# molly.net
KiCad netlist of a schematic drawn in Altium Designer
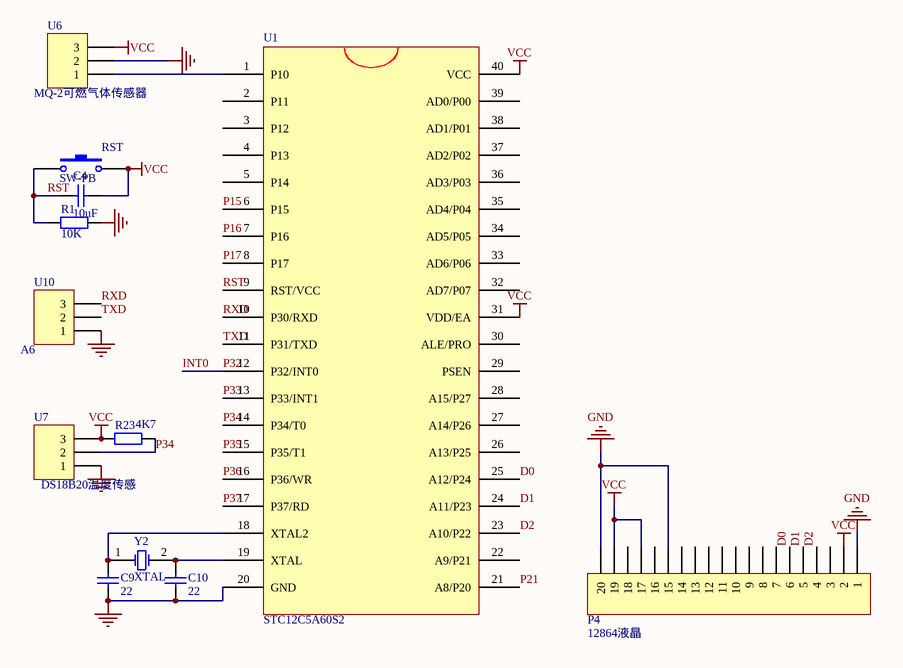
[diagram p0: molly.SchDoc]

(export (version "E")
  (design (tool "Eeschema 10.0.6"))
  (components
    (comp (ref "C4")
      (value "10uF")
      (footprint "CAPR2.54-5.1x3.2")
      (description "Capacitor")
      (fields (field (name "PUBLISHER") "Altium Limited"))
      (libsource (lib "Miscellaneous Devices") (part "cap"))
    )
    (comp (ref "C9")
      (value "22")
      (footprint "2012[0805]")
      (description "Capacitor")
      (fields (field (name "PUBLISHER") "Altium Limited"))
      (libsource (lib "Miscellaneous Devices") (part "Cap"))
    )
    (comp (ref "C10")
      (value "22")
      (footprint "2012[0805]")
      (description "Capacitor")
      (fields (field (name "PUBLISHER") "Altium Limited"))
      (libsource (lib "Miscellaneous Devices") (part "Cap"))
    )
    (comp (ref "P4")
      (value "12864液晶")
      (footprint "HDR1X20")
      (description "Header, 20-Pin")
      (fields (field (name "PUBLISHER") "Altium Limited"))
      (libsource (lib "Miscellaneous Connectors") (part "Header 20"))
    )
    (comp (ref "R1")
      (value "10K")
      (footprint "AXIAL-0.4")
      (description "Resistor")
      (fields (field (name "PUBLISHER") "Altium Limited"))
      (libsource (lib "Miscellaneous Devices") (part "Res2"))
    )
    (comp (ref "R23")
      (value "4K7")
      (footprint "AXIAL-0.4")
      (description "Resistor")
      (fields (field (name "PUBLISHER") "Altium Limited"))
      (libsource (lib "") (part "Res2_1"))
    )
    (comp (ref "RST")
      (value "SW-PB")
      (footprint "KEY_1")
      (description "Switch")
      (fields (field (name "PUBLISHER") "Altium Limited"))
      (libsource (lib "Miscellaneous Devices") (part "SW-PB"))
    )
    (comp (ref "U1")
      (value "STC12C5A60S2")
      (footprint "Dual-In-Line Package:DIP-40")
      (libsource (lib "selfmade") (part "at89s52"))
    )
    (comp (ref "U6")
      (value "MQ-2可燃气体传感器")
      (footprint "HDR1X3")
      (description "Header, 3-Pin")
      (fields (field (name "PUBLISHER") "Altium Limited"))
      (libsource (lib "Miscellaneous Connectors") (part "Header 3"))
    )
    (comp (ref "U7")
      (value "DS18B20温度传感")
      (footprint "HDR1X3")
      (description "Header, 3-Pin")
      (fields (field (name "PUBLISHER") "Altium Limited"))
      (libsource (lib "Miscellaneous Connectors") (part "Header 3"))
    )
    (comp (ref "U10")
      (value "A6")
      (footprint "HDR1X3")
      (description "Header, 3-Pin")
      (fields (field (name "PUBLISHER") "Altium Limited"))
      (libsource (lib "Miscellaneous Connectors") (part "Header 3"))
    )
    (comp (ref "Y2")
      (value "XTAL")
      (footprint "SPST-2")
      (description "Crystal Oscillator")
      (fields (field (name "PUBLISHER") "Altium Limited"))
      (libsource (lib "Miscellaneous Devices") (part "XTAL"))
    )
  )
  (nets
    (net (code "1") (name "/D0") (class "Default")
      (node (ref "P4") (pin "6") (pinfunction "6_6") (pintype "passive"))
      (node (ref "U1") (pin "25") (pinfunction "A12/P24_25") (pintype "passive"))
    )
    (net (code "2") (name "/D1") (class "Default")
      (node (ref "P4") (pin "5") (pinfunction "5_5") (pintype "passive"))
      (node (ref "U1") (pin "24") (pinfunction "A11/P23_24") (pintype "passive"))
    )
    (net (code "3") (name "/D2") (class "Default")
      (node (ref "P4") (pin "4") (pinfunction "4_4") (pintype "passive"))
      (node (ref "U1") (pin "23") (pinfunction "A10/P22_23") (pintype "passive"))
    )
    (net (code "4") (name "/INT0") (class "Default")
      (node (ref "U1") (pin "12") (pinfunction "P32/INT0_12") (pintype "passive"))
    )
    (net (code "5") (name "/P15") (class "Default")
      (node (ref "U1") (pin "6") (pinfunction "P15_6") (pintype "passive"))
    )
    (net (code "6") (name "/P16") (class "Default")
      (node (ref "U1") (pin "7") (pinfunction "P16_7") (pintype "passive"))
    )
    (net (code "7") (name "/P17") (class "Default")
      (node (ref "U1") (pin "8") (pinfunction "P17_8") (pintype "passive"))
    )
    (net (code "8") (name "/P21") (class "Default")
      (node (ref "U1") (pin "21") (pinfunction "A8/P20_21") (pintype "passive"))
    )
    (net (code "9") (name "/P33") (class "Default")
      (node (ref "U1") (pin "13") (pinfunction "P33/INT1_13") (pintype "passive"))
    )
    (net (code "10") (name "/P34") (class "Default")
      (node (ref "R23") (pin "1") (pinfunction "1_1") (pintype "passive"))
      (node (ref "U1") (pin "14") (pinfunction "P34/T0_14") (pintype "passive"))
      (node (ref "U7") (pin "2") (pinfunction "2_2") (pintype "passive"))
    )
    (net (code "11") (name "/P35") (class "Default")
      (node (ref "U1") (pin "15") (pinfunction "P35/T1_15") (pintype "passive"))
    )
    (net (code "12") (name "/P36") (class "Default")
      (node (ref "U1") (pin "16") (pinfunction "P36/WR_16") (pintype "passive"))
    )
    (net (code "13") (name "/P37") (class "Default")
      (node (ref "U1") (pin "17") (pinfunction "P37/RD_17") (pintype "passive"))
    )
    (net (code "14") (name "/RST") (class "Default")
      (node (ref "C4") (pin "1") (pinfunction "1_1") (pintype "passive"))
      (node (ref "R1") (pin "1") (pinfunction "1_1") (pintype "passive"))
      (node (ref "RST") (pin "1") (pinfunction "1_1") (pintype "passive"))
      (node (ref "U1") (pin "9") (pinfunction "RST/VCC_9") (pintype "passive"))
    )
    (net (code "15") (name "/RXD") (class "Default")
      (node (ref "U1") (pin "10") (pinfunction "P30/RXD_10") (pintype "passive"))
      (node (ref "U10") (pin "3") (pinfunction "3_3") (pintype "passive"))
    )
    (net (code "16") (name "/TXD") (class "Default")
      (node (ref "U1") (pin "11") (pinfunction "P31/TXD_11") (pintype "passive"))
      (node (ref "U10") (pin "2") (pinfunction "2_2") (pintype "passive"))
    )
    (net (code "17") (name "GND") (class "Default")
      (node (ref "C10") (pin "2") (pinfunction "2_2") (pintype "passive"))
      (node (ref "C9") (pin "2") (pinfunction "2_2") (pintype "passive"))
      (node (ref "P4") (pin "1") (pinfunction "1_1") (pintype "passive"))
      (node (ref "P4") (pin "15") (pinfunction "15_15") (pintype "passive"))
      (node (ref "P4") (pin "20") (pinfunction "20_20") (pintype "passive"))
      (node (ref "R1") (pin "2") (pinfunction "2_2") (pintype "passive"))
      (node (ref "U1") (pin "20") (pinfunction "GND_20") (pintype "passive"))
      (node (ref "U10") (pin "1") (pinfunction "1_1") (pintype "passive"))
      (node (ref "U6") (pin "2") (pinfunction "2_2") (pintype "passive"))
      (node (ref "U7") (pin "1") (pinfunction "1_1") (pintype "passive"))
    )
    (net (code "18") (name "Net-(U1-P10)") (class "Default")
      (node (ref "U1") (pin "1") (pinfunction "P10_1") (pintype "passive"))
      (node (ref "U6") (pin "1") (pinfunction "1_1") (pintype "passive"))
    )
    (net (code "19") (name "Net-(U1-XTAL)") (class "Default")
      (node (ref "C10") (pin "1") (pinfunction "1_1") (pintype "passive"))
      (node (ref "U1") (pin "19") (pinfunction "XTAL_19") (pintype "passive"))
      (node (ref "Y2") (pin "2") (pinfunction "OSC2_2") (pintype "passive"))
    )
    (net (code "20") (name "Net-(U1-XTAL2)") (class "Default")
      (node (ref "C9") (pin "1") (pinfunction "1_1") (pintype "passive"))
      (node (ref "U1") (pin "18") (pinfunction "XTAL2_18") (pintype "passive"))
      (node (ref "Y2") (pin "1") (pinfunction "OSC1_1") (pintype "passive"))
    )
    (net (code "21") (name "VCC") (class "Default")
      (node (ref "C4") (pin "2") (pinfunction "2_2") (pintype "passive"))
      (node (ref "P4") (pin "17") (pinfunction "17_17") (pintype "passive"))
      (node (ref "P4") (pin "19") (pinfunction "19_19") (pintype "passive"))
      (node (ref "P4") (pin "2") (pinfunction "2_2") (pintype "passive"))
      (node (ref "R23") (pin "2") (pinfunction "2_2") (pintype "passive"))
      (node (ref "RST") (pin "2") (pinfunction "2_2") (pintype "passive"))
      (node (ref "U1") (pin "31") (pinfunction "VDD/EA_31") (pintype "passive"))
      (node (ref "U1") (pin "40") (pinfunction "VCC_40") (pintype "passive"))
      (node (ref "U6") (pin "3") (pinfunction "3_3") (pintype "passive"))
      (node (ref "U7") (pin "3") (pinfunction "3_3") (pintype "passive"))
    )
    (net (code "22") (name "unconnected-(P4-Pad3)") (class "Default")
      (node (ref "P4") (pin "3") (pinfunction "3_3") (pintype "passive"))
    )
    (net (code "23") (name "unconnected-(P4-Pad7)") (class "Default")
      (node (ref "P4") (pin "7") (pinfunction "7_7") (pintype "passive"))
    )
    (net (code "24") (name "unconnected-(P4-Pad8)") (class "Default")
      (node (ref "P4") (pin "8") (pinfunction "8_8") (pintype "passive"))
    )
    (net (code "25") (name "unconnected-(P4-Pad9)") (class "Default")
      (node (ref "P4") (pin "9") (pinfunction "9_9") (pintype "passive"))
    )
    (net (code "26") (name "unconnected-(P4-Pad10)") (class "Default")
      (node (ref "P4") (pin "10") (pinfunction "10_10") (pintype "passive"))
    )
    (net (code "27") (name "unconnected-(P4-Pad11)") (class "Default")
      (node (ref "P4") (pin "11") (pinfunction "11_11") (pintype "passive"))
    )
    (net (code "28") (name "unconnected-(P4-Pad12)") (class "Default")
      (node (ref "P4") (pin "12") (pinfunction "12_12") (pintype "passive"))
    )
    (net (code "29") (name "unconnected-(P4-Pad13)") (class "Default")
      (node (ref "P4") (pin "13") (pinfunction "13_13") (pintype "passive"))
    )
    (net (code "30") (name "unconnected-(P4-Pad14)") (class "Default")
      (node (ref "P4") (pin "14") (pinfunction "14_14") (pintype "passive"))
    )
    (net (code "31") (name "unconnected-(P4-Pad16)") (class "Default")
      (node (ref "P4") (pin "16") (pinfunction "16_16") (pintype "passive"))
    )
    (net (code "32") (name "unconnected-(P4-Pad18)") (class "Default")
      (node (ref "P4") (pin "18") (pinfunction "18_18") (pintype "passive"))
    )
    (net (code "33") (name "unconnected-(U1-A9{slash}P21-Pad22)") (class "Default")
      (node (ref "U1") (pin "22") (pinfunction "A9/P21_22") (pintype "passive"))
    )
    (net (code "34") (name "unconnected-(U1-A13{slash}P25-Pad26)") (class "Default")
      (node (ref "U1") (pin "26") (pinfunction "A13/P25_26") (pintype "passive"))
    )
    (net (code "35") (name "unconnected-(U1-A14{slash}P26-Pad27)") (class "Default")
      (node (ref "U1") (pin "27") (pinfunction "A14/P26_27") (pintype "passive"))
    )
    (net (code "36") (name "unconnected-(U1-A15{slash}P27-Pad28)") (class "Default")
      (node (ref "U1") (pin "28") (pinfunction "A15/P27_28") (pintype "passive"))
    )
    (net (code "37") (name "unconnected-(U1-AD0{slash}P00-Pad39)") (class "Default")
      (node (ref "U1") (pin "39") (pinfunction "AD0/P00_39") (pintype "passive"))
    )
    (net (code "38") (name "unconnected-(U1-AD1{slash}P01-Pad38)") (class "Default")
      (node (ref "U1") (pin "38") (pinfunction "AD1/P01_38") (pintype "passive"))
    )
    (net (code "39") (name "unconnected-(U1-AD2{slash}P02-Pad37)") (class "Default")
      (node (ref "U1") (pin "37") (pinfunction "AD2/P02_37") (pintype "passive"))
    )
    (net (code "40") (name "unconnected-(U1-AD3{slash}P03-Pad36)") (class "Default")
      (node (ref "U1") (pin "36") (pinfunction "AD3/P03_36") (pintype "passive"))
    )
    (net (code "41") (name "unconnected-(U1-AD4{slash}P04-Pad35)") (class "Default")
      (node (ref "U1") (pin "35") (pinfunction "AD4/P04_35") (pintype "passive"))
    )
    (net (code "42") (name "unconnected-(U1-AD5{slash}P05-Pad34)") (class "Default")
      (node (ref "U1") (pin "34") (pinfunction "AD5/P05_34") (pintype "passive"))
    )
    (net (code "43") (name "unconnected-(U1-AD6{slash}P06-Pad33)") (class "Default")
      (node (ref "U1") (pin "33") (pinfunction "AD6/P06_33") (pintype "passive"))
    )
    (net (code "44") (name "unconnected-(U1-AD7{slash}P07-Pad32)") (class "Default")
      (node (ref "U1") (pin "32") (pinfunction "AD7/P07_32") (pintype "passive"))
    )
    (net (code "45") (name "unconnected-(U1-ALE{slash}PRO-Pad30)") (class "Default")
      (node (ref "U1") (pin "30") (pinfunction "ALE/PRO_30") (pintype "passive"))
    )
    (net (code "46") (name "unconnected-(U1-P11-Pad2)") (class "Default")
      (node (ref "U1") (pin "2") (pinfunction "P11_2") (pintype "passive"))
    )
    (net (code "47") (name "unconnected-(U1-P12-Pad3)") (class "Default")
      (node (ref "U1") (pin "3") (pinfunction "P12_3") (pintype "passive"))
    )
    (net (code "48") (name "unconnected-(U1-P13-Pad4)") (class "Default")
      (node (ref "U1") (pin "4") (pinfunction "P13_4") (pintype "passive"))
    )
    (net (code "49") (name "unconnected-(U1-P14-Pad5)") (class "Default")
      (node (ref "U1") (pin "5") (pinfunction "P14_5") (pintype "passive"))
    )
    (net (code "50") (name "unconnected-(U1-PSEN-Pad29)") (class "Default")
      (node (ref "U1") (pin "29") (pinfunction "PSEN_29") (pintype "passive"))
    )
  )
)
